# VIA_PAR_Adapter.net
KiCad netlist of a schematic drawn in EAGLE
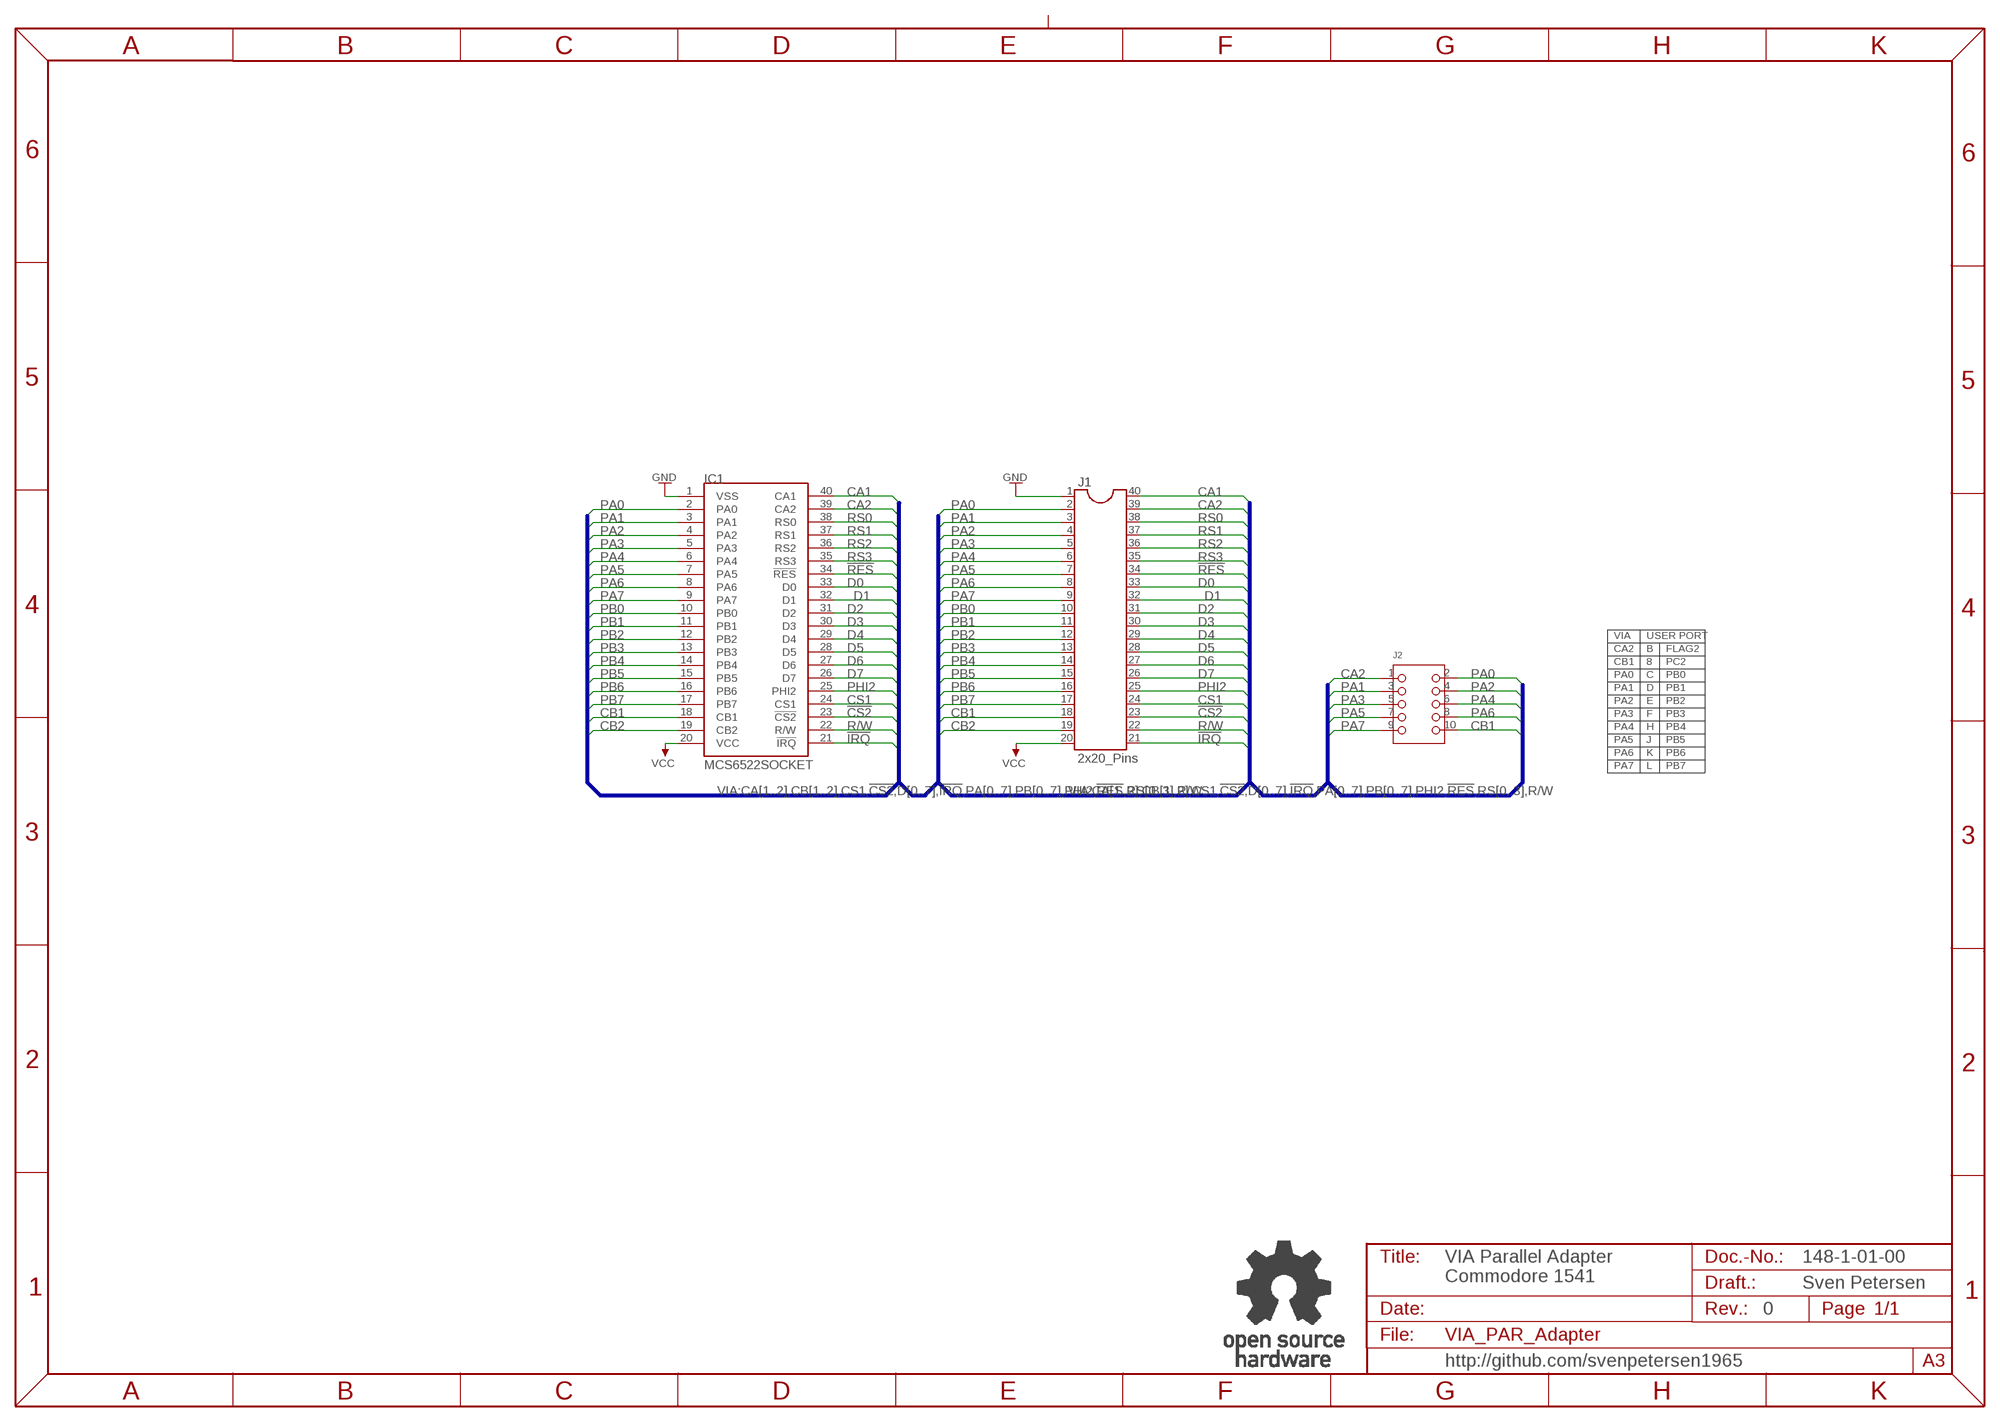
[diagram p0: schematic, sheet 1]

(export (version "E")
  (design (tool "Eeschema 10.0.6"))
  (components
    (comp (ref "IC1")
      (value "MCS6522SOCKET")
      (footprint "eagle-import:GS40P")
      (libsource (lib "eagle-import") (part "MCS6522SOCKET"))
    )
    (comp (ref "J1")
      (value "2x20_Pins")
      (footprint "eagle-import:DIL40_PINS_SS")
      (libsource (lib "eagle-import") (part "IC_DIL40"))
    )
    (comp (ref "J2")
      (value "2X05WV")
      (footprint "eagle-import:2X05WV")
      (libsource (lib "eagle-import") (part "2X05WV"))
    )
    (comp (ref "U$10")
      (value "OPEN_SOURCE_HW")
      (footprint "eagle-import:OPENHW")
      (libsource (lib "eagle-import") (part "OPEN_SOURCE_HW"))
    )
  )
  (nets
    (net (code "1") (name "/CA1") (class "Default")
      (node (ref "IC1") (pin "40") (pinfunction "CA1_40") (pintype "bidirectional"))
      (node (ref "J1") (pin "40") (pinfunction "40_40") (pintype "passive"))
    )
    (net (code "2") (name "/CA2") (class "Default")
      (node (ref "IC1") (pin "39") (pinfunction "CA2_39") (pintype "input"))
      (node (ref "J1") (pin "39") (pinfunction "39_39") (pintype "passive"))
      (node (ref "J2") (pin "1") (pinfunction "1_1") (pintype "passive"))
    )
    (net (code "3") (name "/CB1") (class "Default")
      (node (ref "IC1") (pin "18") (pinfunction "CB1_18") (pintype "bidirectional"))
      (node (ref "J1") (pin "18") (pinfunction "18_18") (pintype "passive"))
      (node (ref "J2") (pin "10") (pinfunction "10_10") (pintype "passive"))
    )
    (net (code "4") (name "/CB2") (class "Default")
      (node (ref "IC1") (pin "19") (pinfunction "CB2_19") (pintype "bidirectional"))
      (node (ref "J1") (pin "19") (pinfunction "19_19") (pintype "passive"))
    )
    (net (code "5") (name "/CS1") (class "Default")
      (node (ref "IC1") (pin "24") (pinfunction "CS1_24") (pintype "input"))
      (node (ref "J1") (pin "24") (pinfunction "24_24") (pintype "passive"))
    )
    (net (code "6") (name "/D0") (class "Default")
      (node (ref "IC1") (pin "33") (pinfunction "D0_33") (pintype "bidirectional"))
      (node (ref "J1") (pin "33") (pinfunction "33_33") (pintype "passive"))
    )
    (net (code "7") (name "/D1") (class "Default")
      (node (ref "IC1") (pin "32") (pinfunction "D1_32") (pintype "bidirectional"))
      (node (ref "J1") (pin "32") (pinfunction "32_32") (pintype "passive"))
    )
    (net (code "8") (name "/D2") (class "Default")
      (node (ref "IC1") (pin "31") (pinfunction "D2_31") (pintype "bidirectional"))
      (node (ref "J1") (pin "31") (pinfunction "31_31") (pintype "passive"))
    )
    (net (code "9") (name "/D3") (class "Default")
      (node (ref "IC1") (pin "30") (pinfunction "D3_30") (pintype "bidirectional"))
      (node (ref "J1") (pin "30") (pinfunction "30_30") (pintype "passive"))
    )
    (net (code "10") (name "/D4") (class "Default")
      (node (ref "IC1") (pin "29") (pinfunction "D4_29") (pintype "bidirectional"))
      (node (ref "J1") (pin "29") (pinfunction "29_29") (pintype "passive"))
    )
    (net (code "11") (name "/D5") (class "Default")
      (node (ref "IC1") (pin "28") (pinfunction "D5_28") (pintype "bidirectional"))
      (node (ref "J1") (pin "28") (pinfunction "28_28") (pintype "passive"))
    )
    (net (code "12") (name "/D6") (class "Default")
      (node (ref "IC1") (pin "27") (pinfunction "D6_27") (pintype "bidirectional"))
      (node (ref "J1") (pin "27") (pinfunction "27_27") (pintype "passive"))
    )
    (net (code "13") (name "/D7") (class "Default")
      (node (ref "IC1") (pin "26") (pinfunction "D7_26") (pintype "bidirectional"))
      (node (ref "J1") (pin "26") (pinfunction "26_26") (pintype "passive"))
    )
    (net (code "14") (name "/PA0") (class "Default")
      (node (ref "IC1") (pin "2") (pinfunction "PA0_2") (pintype "bidirectional"))
      (node (ref "J1") (pin "2") (pinfunction "2_2") (pintype "passive"))
      (node (ref "J2") (pin "2") (pinfunction "2_2") (pintype "passive"))
    )
    (net (code "15") (name "/PA1") (class "Default")
      (node (ref "IC1") (pin "3") (pinfunction "PA1_3") (pintype "bidirectional"))
      (node (ref "J1") (pin "3") (pinfunction "3_3") (pintype "passive"))
      (node (ref "J2") (pin "3") (pinfunction "3_3") (pintype "passive"))
    )
    (net (code "16") (name "/PA2") (class "Default")
      (node (ref "IC1") (pin "4") (pinfunction "PA2_4") (pintype "bidirectional"))
      (node (ref "J1") (pin "4") (pinfunction "4_4") (pintype "passive"))
      (node (ref "J2") (pin "4") (pinfunction "4_4") (pintype "passive"))
    )
    (net (code "17") (name "/PA3") (class "Default")
      (node (ref "IC1") (pin "5") (pinfunction "PA3_5") (pintype "bidirectional"))
      (node (ref "J1") (pin "5") (pinfunction "5_5") (pintype "passive"))
      (node (ref "J2") (pin "5") (pinfunction "5_5") (pintype "passive"))
    )
    (net (code "18") (name "/PA4") (class "Default")
      (node (ref "IC1") (pin "6") (pinfunction "PA4_6") (pintype "bidirectional"))
      (node (ref "J1") (pin "6") (pinfunction "6_6") (pintype "passive"))
      (node (ref "J2") (pin "6") (pinfunction "6_6") (pintype "passive"))
    )
    (net (code "19") (name "/PA5") (class "Default")
      (node (ref "IC1") (pin "7") (pinfunction "PA5_7") (pintype "bidirectional"))
      (node (ref "J1") (pin "7") (pinfunction "7_7") (pintype "passive"))
      (node (ref "J2") (pin "7") (pinfunction "7_7") (pintype "passive"))
    )
    (net (code "20") (name "/PA6") (class "Default")
      (node (ref "IC1") (pin "8") (pinfunction "PA6_8") (pintype "bidirectional"))
      (node (ref "J1") (pin "8") (pinfunction "8_8") (pintype "passive"))
      (node (ref "J2") (pin "8") (pinfunction "8_8") (pintype "passive"))
    )
    (net (code "21") (name "/PA7") (class "Default")
      (node (ref "IC1") (pin "9") (pinfunction "PA7_9") (pintype "bidirectional"))
      (node (ref "J1") (pin "9") (pinfunction "9_9") (pintype "passive"))
      (node (ref "J2") (pin "9") (pinfunction "9_9") (pintype "passive"))
    )
    (net (code "22") (name "/PB0") (class "Default")
      (node (ref "IC1") (pin "10") (pinfunction "PB0_10") (pintype "bidirectional"))
      (node (ref "J1") (pin "10") (pinfunction "10_10") (pintype "passive"))
    )
    (net (code "23") (name "/PB1") (class "Default")
      (node (ref "IC1") (pin "11") (pinfunction "PB1_11") (pintype "bidirectional"))
      (node (ref "J1") (pin "11") (pinfunction "11_11") (pintype "passive"))
    )
    (net (code "24") (name "/PB2") (class "Default")
      (node (ref "IC1") (pin "12") (pinfunction "PB2_12") (pintype "bidirectional"))
      (node (ref "J1") (pin "12") (pinfunction "12_12") (pintype "passive"))
    )
    (net (code "25") (name "/PB3") (class "Default")
      (node (ref "IC1") (pin "13") (pinfunction "PB3_13") (pintype "bidirectional"))
      (node (ref "J1") (pin "13") (pinfunction "13_13") (pintype "passive"))
    )
    (net (code "26") (name "/PB4") (class "Default")
      (node (ref "IC1") (pin "14") (pinfunction "PB4_14") (pintype "bidirectional"))
      (node (ref "J1") (pin "14") (pinfunction "14_14") (pintype "passive"))
    )
    (net (code "27") (name "/PB5") (class "Default")
      (node (ref "IC1") (pin "15") (pinfunction "PB5_15") (pintype "bidirectional"))
      (node (ref "J1") (pin "15") (pinfunction "15_15") (pintype "passive"))
    )
    (net (code "28") (name "/PB6") (class "Default")
      (node (ref "IC1") (pin "16") (pinfunction "PB6_16") (pintype "bidirectional"))
      (node (ref "J1") (pin "16") (pinfunction "16_16") (pintype "passive"))
    )
    (net (code "29") (name "/PB7") (class "Default")
      (node (ref "IC1") (pin "17") (pinfunction "PB7_17") (pintype "bidirectional"))
      (node (ref "J1") (pin "17") (pinfunction "17_17") (pintype "passive"))
    )
    (net (code "30") (name "/PHI2") (class "Default")
      (node (ref "IC1") (pin "25") (pinfunction "PHI2_25") (pintype "input"))
      (node (ref "J1") (pin "25") (pinfunction "25_25") (pintype "passive"))
    )
    (net (code "31") (name "/RS0") (class "Default")
      (node (ref "IC1") (pin "38") (pinfunction "RS0_38") (pintype "input"))
      (node (ref "J1") (pin "38") (pinfunction "38_38") (pintype "passive"))
    )
    (net (code "32") (name "/RS1") (class "Default")
      (node (ref "IC1") (pin "37") (pinfunction "RS1_37") (pintype "input"))
      (node (ref "J1") (pin "37") (pinfunction "37_37") (pintype "passive"))
    )
    (net (code "33") (name "/RS2") (class "Default")
      (node (ref "IC1") (pin "36") (pinfunction "RS2_36") (pintype "input"))
      (node (ref "J1") (pin "36") (pinfunction "36_36") (pintype "passive"))
    )
    (net (code "34") (name "/RS3") (class "Default")
      (node (ref "IC1") (pin "35") (pinfunction "RS3_35") (pintype "input"))
      (node (ref "J1") (pin "35") (pinfunction "35_35") (pintype "passive"))
    )
    (net (code "35") (name "/R{slash}W") (class "Default")
      (node (ref "IC1") (pin "22") (pinfunction "R/W_22") (pintype "input"))
      (node (ref "J1") (pin "22") (pinfunction "22_22") (pintype "passive"))
    )
    (net (code "37") (name "/~{CS2}") (class "Default")
      (node (ref "IC1") (pin "23") (pinfunction "~{CS2}_23") (pintype "input"))
      (node (ref "J1") (pin "23") (pinfunction "23_23") (pintype "passive"))
    )
    (net (code "38") (name "/~{IRQ}") (class "Default")
      (node (ref "IC1") (pin "21") (pinfunction "~{IRQ}_21") (pintype "output"))
      (node (ref "J1") (pin "21") (pinfunction "21_21") (pintype "passive"))
    )
    (net (code "39") (name "/~{RES}") (class "Default")
      (node (ref "IC1") (pin "34") (pinfunction "~{RES}_34") (pintype "input"))
      (node (ref "J1") (pin "34") (pinfunction "34_34") (pintype "passive"))
    )
    (net (code "40") (name "GND") (class "Default")
      (node (ref "IC1") (pin "1") (pinfunction "VSS_1") (pintype "power_in"))
      (node (ref "J1") (pin "1") (pinfunction "1_1") (pintype "passive"))
    )
    (net (code "41") (name "VCC") (class "Default")
      (node (ref "IC1") (pin "20") (pinfunction "VCC_20") (pintype "power_in"))
      (node (ref "J1") (pin "20") (pinfunction "20_20") (pintype "passive"))
    )
  )
)
